# v1_0.net
KiCad netlist of a schematic drawn in Altium Designer
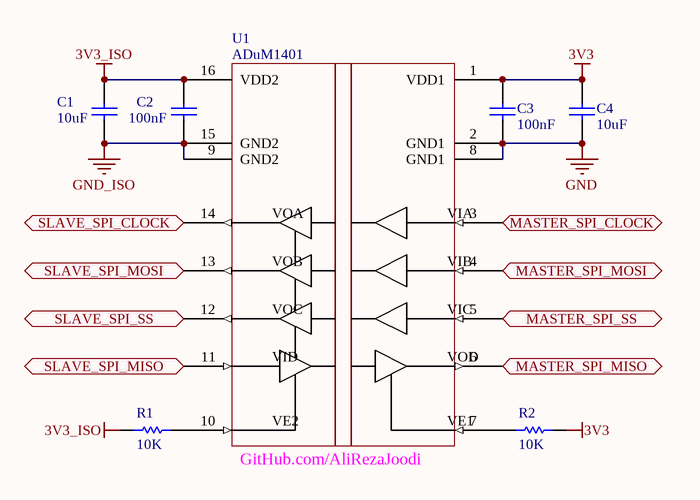
[diagram p0: v1.0.SchDoc]

(export (version "E")
  (design (tool "Eeschema 10.0.6"))
  (components
    (comp (ref "C1")
      (value "10uF")
      (footprint "Capacitor_Ceramic:SMD_0805")
      (description "Capacitor, Ceramic Multilayer")
      (libsource (lib "General") (part "Capacitor_Ceramic"))
    )
    (comp (ref "C2")
      (value "100nF")
      (footprint "Capacitor_Ceramic:SMD_0805")
      (description "Capacitor, Ceramic Multilayer")
      (libsource (lib "General") (part "Capacitor_Ceramic"))
    )
    (comp (ref "C3")
      (value "100nF")
      (footprint "Capacitor_Ceramic:SMD_0805")
      (description "Capacitor, Ceramic Multilayer")
      (libsource (lib "General") (part "Capacitor_Ceramic"))
    )
    (comp (ref "C4")
      (value "10uF")
      (footprint "Capacitor_Ceramic:SMD_0805")
      (description "Capacitor, Ceramic Multilayer")
      (libsource (lib "General") (part "Capacitor_Ceramic"))
    )
    (comp (ref "R1")
      (value "10K")
      (footprint "SMD_0805")
      (description "Resistor, 1/8W, 5%")
      (libsource (lib "General") (part "Resistor"))
    )
    (comp (ref "R2")
      (value "10K")
      (footprint "SMD_0805")
      (description "Resistor, 1/8W, 5%")
      (libsource (lib "General") (part "Resistor"))
    )
    (comp (ref "U1")
      (value "ADuM1401")
      (footprint "SOIC127P1032X265-16N")
      (description "IC, Quad-Channel Digital Isolators")
      (fields (field (name "1_PART NUMBER") "ADUM1401BRWZ"))
      (libsource (lib "IC") (part "Isolator_ADuM1401"))
    )
  )
  (nets
    (net (code "1") (name "/MASTER_SPI_CLOCK") (class "Default")
      (node (ref "U1") (pin "3") (pinfunction "VIA_3") (pintype "input"))
    )
    (net (code "2") (name "/MASTER_SPI_MISO") (class "Default")
      (node (ref "U1") (pin "6") (pinfunction "VOD_6") (pintype "output"))
    )
    (net (code "3") (name "/MASTER_SPI_MOSI") (class "Default")
      (node (ref "U1") (pin "4") (pinfunction "VIB_4") (pintype "input"))
    )
    (net (code "4") (name "/MASTER_SPI_SS") (class "Default")
      (node (ref "U1") (pin "5") (pinfunction "VIC_5") (pintype "input"))
    )
    (net (code "5") (name "/SLAVE_SPI_CLOCK") (class "Default")
      (node (ref "U1") (pin "14") (pinfunction "VOA_14") (pintype "output"))
    )
    (net (code "6") (name "/SLAVE_SPI_MISO") (class "Default")
      (node (ref "U1") (pin "11") (pinfunction "VID_11") (pintype "input"))
    )
    (net (code "7") (name "/SLAVE_SPI_MOSI") (class "Default")
      (node (ref "U1") (pin "13") (pinfunction "VOB_13") (pintype "output"))
    )
    (net (code "8") (name "/SLAVE_SPI_SS") (class "Default")
      (node (ref "U1") (pin "12") (pinfunction "VOC_12") (pintype "output"))
    )
    (net (code "9") (name "3V3") (class "Default")
      (node (ref "C3") (pin "2") (pinfunction "2_2") (pintype "passive"))
      (node (ref "C4") (pin "1") (pinfunction "1_1") (pintype "passive"))
      (node (ref "R2") (pin "2") (pinfunction "2_2") (pintype "passive"))
      (node (ref "U1") (pin "1") (pinfunction "VDD1_1") (pintype "passive"))
    )
    (net (code "10") (name "3V3_ISO") (class "Default")
      (node (ref "C1") (pin "1") (pinfunction "1_1") (pintype "passive"))
      (node (ref "C2") (pin "2") (pinfunction "2_2") (pintype "passive"))
      (node (ref "R1") (pin "1") (pinfunction "1_1") (pintype "passive"))
      (node (ref "U1") (pin "16") (pinfunction "VDD2_16") (pintype "passive"))
    )
    (net (code "11") (name "GND") (class "Default")
      (node (ref "C3") (pin "1") (pinfunction "1_1") (pintype "passive"))
      (node (ref "C4") (pin "2") (pinfunction "2_2") (pintype "passive"))
      (node (ref "U1") (pin "2") (pinfunction "GND1_2") (pintype "passive"))
      (node (ref "U1") (pin "8") (pinfunction "GND1_8") (pintype "passive"))
    )
    (net (code "12") (name "GND_ISO") (class "Default")
      (node (ref "C1") (pin "2") (pinfunction "2_2") (pintype "passive"))
      (node (ref "C2") (pin "1") (pinfunction "1_1") (pintype "passive"))
      (node (ref "U1") (pin "15") (pinfunction "GND2_15") (pintype "passive"))
      (node (ref "U1") (pin "9") (pinfunction "GND2_9") (pintype "passive"))
    )
    (net (code "13") (name "Net-(U1-VE1)") (class "Default")
      (node (ref "R2") (pin "1") (pinfunction "1_1") (pintype "passive"))
      (node (ref "U1") (pin "7") (pinfunction "VE1_7") (pintype "input"))
    )
    (net (code "14") (name "Net-(U1-VE2)") (class "Default")
      (node (ref "R1") (pin "2") (pinfunction "2_2") (pintype "passive"))
      (node (ref "U1") (pin "10") (pinfunction "VE2_10") (pintype "input"))
    )
  )
)
